# Sheet4_LCD.net
KiCad netlist of a schematic drawn in Altium Designer
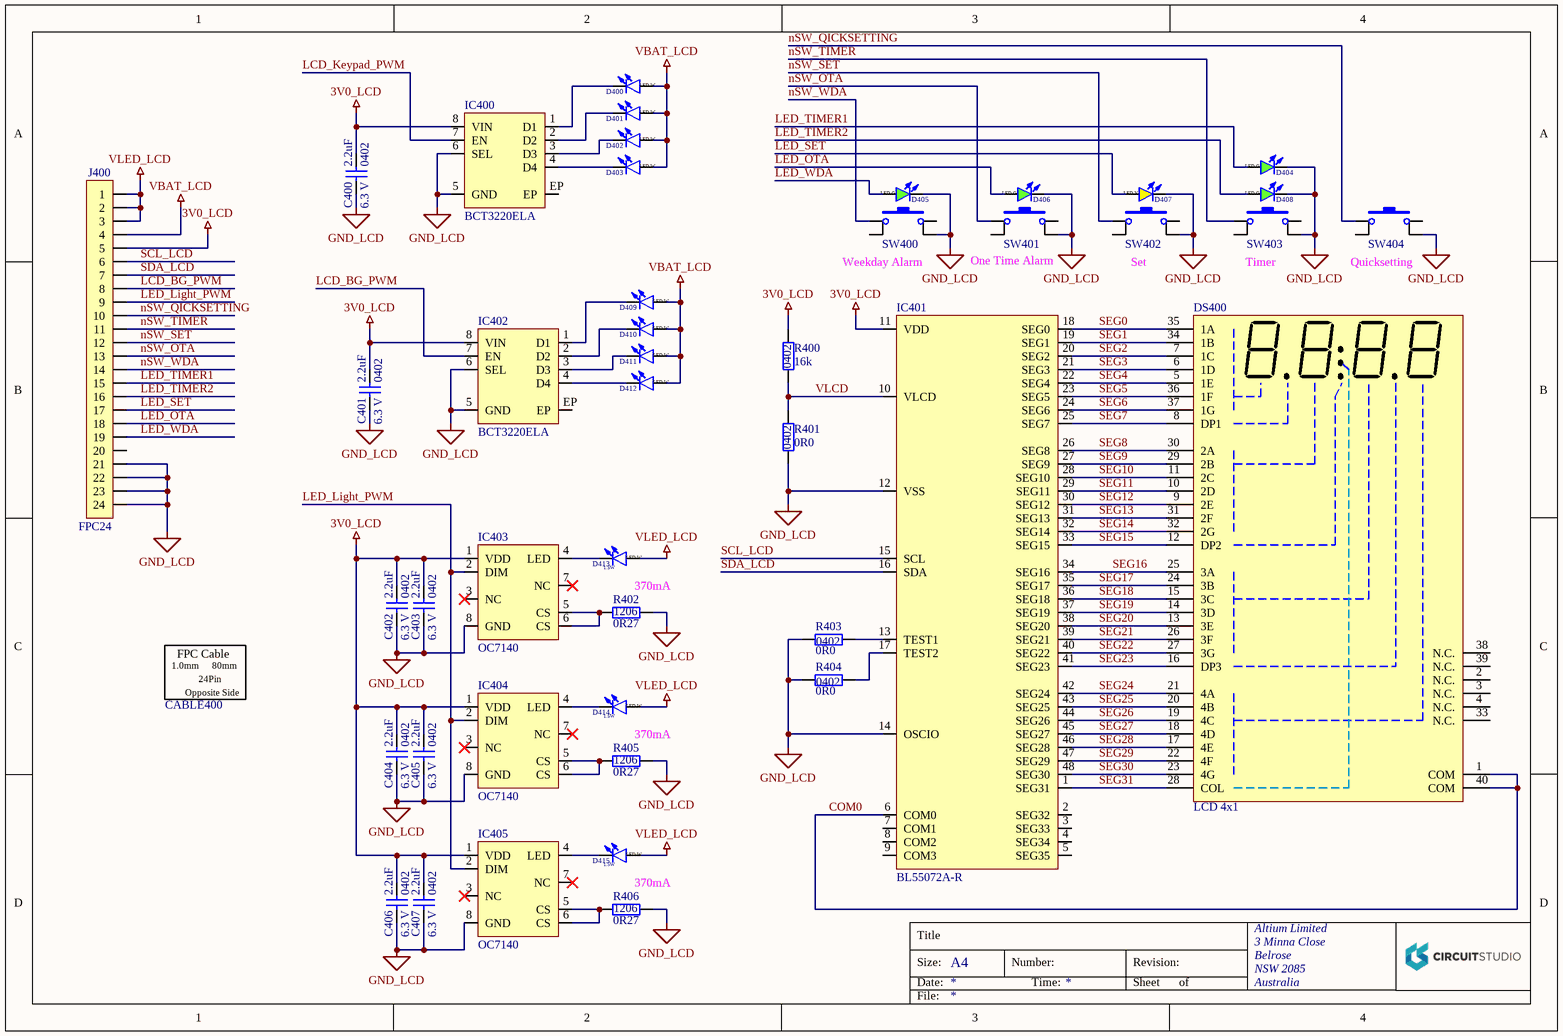
[diagram p0: Sheet4_LCD.SchDoc]

(export (version "E")
  (design (tool "Eeschema 10.0.6"))
  (components
    (comp (ref "C400")
      (value "C 2.2uF 0402 6.3V")
      (footprint "0402")
      (description "CAP CER 2.2UF 6.3V X6T 0402")
      (fields
        (field (name "MANUFACTURER") "Murata Electronics")
        (field (name "MANUFACTURER PART NUMBER") "GRM155D80J225ME95D")
        (field (name "CAPACITANCE") "2.2uF")
        (field (name "VOLTAGE") "6.3 V")
      )
      (libsource (lib "CS_Part_Library") (part "CAP_2.2uF_6V3_0402"))
    )
    (comp (ref "C401")
      (value "C 2.2uF 0402 6.3V")
      (footprint "0402")
      (description "CAP CER 2.2UF 6.3V X6T 0402")
      (fields
        (field (name "MANUFACTURER") "Murata Electronics")
        (field (name "MANUFACTURER PART NUMBER") "GRM155D80J225ME95D")
        (field (name "CAPACITANCE") "2.2uF")
        (field (name "VOLTAGE") "6.3 V")
      )
      (libsource (lib "CS_Part_Library") (part "CAP_2.2uF_6V3_0402"))
    )
    (comp (ref "C402")
      (value "C 2.2uF 0402 6.3V")
      (footprint "0402")
      (description "CAP CER 2.2UF 6.3V X6T 0402")
      (fields
        (field (name "MANUFACTURER") "Murata Electronics")
        (field (name "MANUFACTURER PART NUMBER") "GRM155D80J225ME95D")
        (field (name "CAPACITANCE") "2.2uF")
        (field (name "VOLTAGE") "6.3 V")
      )
      (libsource (lib "CS_Part_Library") (part "CAP_2.2uF_6V3_0402"))
    )
    (comp (ref "C403")
      (value "C 2.2uF 0402 6.3V")
      (footprint "0402")
      (description "CAP CER 2.2UF 6.3V X6T 0402")
      (fields
        (field (name "MANUFACTURER") "Murata Electronics")
        (field (name "MANUFACTURER PART NUMBER") "GRM155D80J225ME95D")
        (field (name "CAPACITANCE") "2.2uF")
        (field (name "VOLTAGE") "6.3 V")
      )
      (libsource (lib "CS_Part_Library") (part "CAP_2.2uF_6V3_0402"))
    )
    (comp (ref "C404")
      (value "C 2.2uF 0402 6.3V")
      (footprint "0402")
      (description "CAP CER 2.2UF 6.3V X6T 0402")
      (fields
        (field (name "MANUFACTURER") "Murata Electronics")
        (field (name "MANUFACTURER PART NUMBER") "GRM155D80J225ME95D")
        (field (name "CAPACITANCE") "2.2uF")
        (field (name "VOLTAGE") "6.3 V")
      )
      (libsource (lib "CS_Part_Library") (part "CAP_2.2uF_6V3_0402"))
    )
    (comp (ref "C405")
      (value "C 2.2uF 0402 6.3V")
      (footprint "0402")
      (description "CAP CER 2.2UF 6.3V X6T 0402")
      (fields
        (field (name "MANUFACTURER") "Murata Electronics")
        (field (name "MANUFACTURER PART NUMBER") "GRM155D80J225ME95D")
        (field (name "CAPACITANCE") "2.2uF")
        (field (name "VOLTAGE") "6.3 V")
      )
      (libsource (lib "CS_Part_Library") (part "CAP_2.2uF_6V3_0402"))
    )
    (comp (ref "C406")
      (value "C 2.2uF 0402 6.3V")
      (footprint "0402")
      (description "CAP CER 2.2UF 6.3V X6T 0402")
      (fields
        (field (name "MANUFACTURER") "Murata Electronics")
        (field (name "MANUFACTURER PART NUMBER") "GRM155D80J225ME95D")
        (field (name "CAPACITANCE") "2.2uF")
        (field (name "VOLTAGE") "6.3 V")
      )
      (libsource (lib "CS_Part_Library") (part "CAP_2.2uF_6V3_0402"))
    )
    (comp (ref "C407")
      (value "C 2.2uF 0402 6.3V")
      (footprint "0402")
      (description "CAP CER 2.2UF 6.3V X6T 0402")
      (fields
        (field (name "MANUFACTURER") "Murata Electronics")
        (field (name "MANUFACTURER PART NUMBER") "GRM155D80J225ME95D")
        (field (name "CAPACITANCE") "2.2uF")
        (field (name "VOLTAGE") "6.3 V")
      )
      (libsource (lib "CS_Part_Library") (part "CAP_2.2uF_6V3_0402"))
    )
    (comp (ref "CABLE400")
      (value "FPC24p80mm")
      (description "FPC Cable 1mm Pitch 24Pin 80mm Opposite Sides")
      (fields
        (field (name "MANUFACTURER") "LX")
        (field (name "MANUFACTURER PART NUMBER") "C50299")
        (field (name "PITCH") "1.0mm")
        (field (name "LENGTH") "80mm")
        (field (name "MODE") "Opposite Side")
        (field (name "NOOFPINS") "24Pin")
      )
      (libsource (lib "Symbols") (part "CABLE_FPC24_80"))
    )
    (comp (ref "D400")
      (value "LED W")
      (footprint "LED_99-218UMC_side")
      (description "LED WHITE SIDE SMD")
      (fields
        (field (name "MANUFACTURER") "Everlight Elec")
        (field (name "MANUFACTURER PART NUMBER") "99-218UMC/1637CD/TR8-T")
      )
      (libsource (lib "CS_Part_Library") (part "D_LED_White_s"))
    )
    (comp (ref "D401")
      (value "LED W")
      (footprint "LED_99-218UMC_side")
      (description "LED WHITE SIDE SMD")
      (fields
        (field (name "MANUFACTURER") "Everlight Elec")
        (field (name "MANUFACTURER PART NUMBER") "99-218UMC/1637CD/TR8-T")
      )
      (libsource (lib "CS_Part_Library") (part "D_LED_White_s"))
    )
    (comp (ref "D402")
      (value "LED W")
      (footprint "LED_99-218UMC_side")
      (description "LED WHITE SIDE SMD")
      (fields
        (field (name "MANUFACTURER") "Everlight Elec")
        (field (name "MANUFACTURER PART NUMBER") "99-218UMC/1637CD/TR8-T")
      )
      (libsource (lib "CS_Part_Library") (part "D_LED_White_s"))
    )
    (comp (ref "D403")
      (value "LED W")
      (footprint "LED_99-218UMC_side")
      (description "LED WHITE SIDE SMD")
      (fields
        (field (name "MANUFACTURER") "Everlight Elec")
        (field (name "MANUFACTURER PART NUMBER") "99-218UMC/1637CD/TR8-T")
      )
      (libsource (lib "CS_Part_Library") (part "D_LED_White_s"))
    )
    (comp (ref "D404")
      (value "LED G")
      (footprint "LED_0603")
      (description "LED GREEN DIFFUSED 0603 SMD")
      (fields
        (field (name "MANUFACTURER") "OSRAM Opto Semiconductors Inc.")
        (field (name "MANUFACTURER PART NUMBER") "LT Q39G-Q1OO-25-1")
      )
      (libsource (lib "CS_Part_Library") (part "D_LED_Green_0603"))
    )
    (comp (ref "D405")
      (value "LED G")
      (footprint "LED_0603")
      (description "LED GREEN DIFFUSED 0603 SMD")
      (fields
        (field (name "MANUFACTURER") "OSRAM Opto Semiconductors Inc.")
        (field (name "MANUFACTURER PART NUMBER") "LT Q39G-Q1OO-25-1")
      )
      (libsource (lib "CS_Part_Library") (part "D_LED_Green_0603"))
    )
    (comp (ref "D406")
      (value "LED G")
      (footprint "LED_0603")
      (description "LED GREEN DIFFUSED 0603 SMD")
      (fields
        (field (name "MANUFACTURER") "OSRAM Opto Semiconductors Inc.")
        (field (name "MANUFACTURER PART NUMBER") "LT Q39G-Q1OO-25-1")
      )
      (libsource (lib "CS_Part_Library") (part "D_LED_Green_0603"))
    )
    (comp (ref "D407")
      (value "LED Y")
      (footprint "LED_0603")
      (description "LED YELLOW DIFFUSED")
      (fields
        (field (name "MANUFACTURER") "Stanley Electric Co")
        (field (name "MANUFACTURER PART NUMBER") "FKY1111C-TR")
      )
      (libsource (lib "CS_Part_Library") (part "D_LED_Yellow_0603"))
    )
    (comp (ref "D408")
      (value "LED G")
      (footprint "LED_0603")
      (description "LED GREEN DIFFUSED 0603 SMD")
      (fields
        (field (name "MANUFACTURER") "OSRAM Opto Semiconductors Inc.")
        (field (name "MANUFACTURER PART NUMBER") "LT Q39G-Q1OO-25-1")
      )
      (libsource (lib "CS_Part_Library") (part "D_LED_Green_0603"))
    )
    (comp (ref "D409")
      (value "LED W")
      (footprint "LED_99-218UMC_side")
      (description "LED WHITE SIDE SMD")
      (fields
        (field (name "MANUFACTURER") "Everlight Elec")
        (field (name "MANUFACTURER PART NUMBER") "99-218UMC/1637CD/TR8-T")
      )
      (libsource (lib "CS_Part_Library") (part "D_LED_White_s"))
    )
    (comp (ref "D410")
      (value "LED W")
      (footprint "LED_99-218UMC_side")
      (description "LED WHITE SIDE SMD")
      (fields
        (field (name "MANUFACTURER") "Everlight Elec")
        (field (name "MANUFACTURER PART NUMBER") "99-218UMC/1637CD/TR8-T")
      )
      (libsource (lib "CS_Part_Library") (part "D_LED_White_s"))
    )
    (comp (ref "D411")
      (value "LED W")
      (footprint "LED_99-218UMC_side")
      (description "LED WHITE SIDE SMD")
      (fields
        (field (name "MANUFACTURER") "Everlight Elec")
        (field (name "MANUFACTURER PART NUMBER") "99-218UMC/1637CD/TR8-T")
      )
      (libsource (lib "CS_Part_Library") (part "D_LED_White_s"))
    )
    (comp (ref "D412")
      (value "LED W")
      (footprint "LED_99-218UMC_side")
      (description "LED WHITE SIDE SMD")
      (fields
        (field (name "MANUFACTURER") "Everlight Elec")
        (field (name "MANUFACTURER PART NUMBER") "99-218UMC/1637CD/TR8-T")
      )
      (libsource (lib "CS_Part_Library") (part "D_LED_White_s"))
    )
    (comp (ref "D413")
      (value "LED W")
      (footprint "LED_3.5x3.15")
      (description "LED XLAMP WARM WHITE 3250K 4SMD")
      (fields
        (field (name "MANUFACTURER") "CreeLED, Inc.")
        (field (name "MANUFACTURER PART NUMBER") "MLEAWT-A1-0000-0003F7")
        (field (name "POWER") "1.5W")
      )
      (libsource (lib "CS_Part_Library") (part "D_LED_W_HP"))
    )
    (comp (ref "D414")
      (value "LED W")
      (footprint "LED_3.5x3.15")
      (description "LED XLAMP WARM WHITE 3250K 4SMD")
      (fields
        (field (name "MANUFACTURER") "CreeLED, Inc.")
        (field (name "MANUFACTURER PART NUMBER") "MLEAWT-A1-0000-0003F7")
        (field (name "POWER") "1.5W")
      )
      (libsource (lib "CS_Part_Library") (part "D_LED_W_HP"))
    )
    (comp (ref "D415")
      (value "LED W")
      (footprint "LED_3.5x3.15")
      (description "LED XLAMP WARM WHITE 3250K 4SMD")
      (fields
        (field (name "MANUFACTURER") "CreeLED, Inc.")
        (field (name "MANUFACTURER PART NUMBER") "MLEAWT-A1-0000-0003F7")
        (field (name "POWER") "1.5W")
      )
      (libsource (lib "CS_Part_Library") (part "D_LED_W_HP"))
    )
    (comp (ref "DS400")
      (value "LCD 4x1")
      (footprint "DISPL_7SEG_4")
      (description "LCD MOD 4 DIG 4 X 1 REFLECTIVE")
      (fields
        (field (name "MANUFACTURER") "Varitronix")
        (field (name "MANUFACTURER PART NUMBER") "VI-402-DP-RC-S")
      )
      (libsource (lib "Symbols") (part "DISPL_7SEG_4x1"))
    )
    (comp (ref "IC400")
      (value "BCT3220ELA")
      (footprint "VDFN-8-EP_2x2")
      (description "IC LED DRIVER 4 CH")
      (fields
        (field (name "MANUFACTURER") "BROADCHIP")
        (field (name "MANUFACTURER PART NUMBER") "BCT3220ELA-TR")
      )
      (libsource (lib "Symbols") (part "IC_LED_cntr_BCT3220ELA"))
    )
    (comp (ref "IC401")
      (value "BL55072A-R")
      (footprint "TSSOP-48")
      (description "IC LCD DRIVER 36SEG TSSOP-48")
      (fields (field (name "MANUFACTURER") "BL(Shanghai Belling)"))
      (libsource (lib "Symbols") (part "IC_LCD_cntr_BL55072A-R"))
    )
    (comp (ref "IC402")
      (value "BCT3220ELA")
      (footprint "VDFN-8-EP_2x2")
      (description "IC LED DRIVER 4 CH")
      (fields
        (field (name "MANUFACTURER") "BROADCHIP")
        (field (name "MANUFACTURER PART NUMBER") "BCT3220ELA-TR")
      )
      (libsource (lib "Symbols") (part "IC_LED_cntr_BCT3220ELA"))
    )
    (comp (ref "IC403")
      (value "OC7140")
      (footprint "SOIC-8-EP")
      (description "IC LED DRIVER 1 CH 2A ESOP8")
      (fields (field (name "MANUFACTURER") "OCX"))
      (libsource (lib "CS_Part_Library") (part "IC_LED_cntr_OC7140"))
    )
    (comp (ref "IC404")
      (value "OC7140")
      (footprint "SOIC-8-EP")
      (description "IC LED DRIVER 1 CH 2A ESOP8")
      (fields (field (name "MANUFACTURER") "OCX"))
      (libsource (lib "CS_Part_Library") (part "IC_LED_cntr_OC7140"))
    )
    (comp (ref "IC405")
      (value "OC7140")
      (footprint "SOIC-8-EP")
      (description "IC LED DRIVER 1 CH 2A ESOP8")
      (fields (field (name "MANUFACTURER") "OCX"))
      (libsource (lib "CS_Part_Library") (part "IC_LED_cntr_OC7140"))
    )
    (comp (ref "J400")
      (value "FPC24")
      (footprint "J_FPC_522712479")
      (description "CONN FPC BOT 24 PIN 1mm Pitch")
      (fields (field (name "MANUFACTURER") "MOLEX") (field (name "MANUFACTURER PART NUMBER") "522712479"))
      (libsource (lib "Symbols") (part "J_FPC24_DS"))
    )
    (comp (ref "R400")
      (value "R 16k 0402")
      (footprint "0402")
      (description "RES 16K OHM 1% 1/16W 0402")
      (fields
        (field (name "MANUFACTURER") "Stackpole Electronics Inc")
        (field (name "MANUFACTURER PART NUMBER") "RMCF0402FT16K0")
        (field (name "RESISTANCE") "16k")
      )
      (libsource (lib "CS_Part_Library") (part "R_16k_0402"))
    )
    (comp (ref "R401")
      (value "R 0R0 0402")
      (footprint "0402")
      (description "RES 0 OHM JUMPER 1/16W 0402")
      (fields
        (field (name "MANUFACTURER") "Stackpole Electronics Inc")
        (field (name "MANUFACTURER PART NUMBER") "RMCF0402ZT0R00")
        (field (name "RESISTANCE") "0R0")
      )
      (libsource (lib "") (part "R_0R0_0402_1"))
    )
    (comp (ref "R402")
      (value "R 0R27 1206")
      (footprint "1206")
      (description "RES 0.27 OHM 1% 1/3W 1206")
      (fields
        (field (name "MANUFACTURER") "RALEC")
        (field (name "MANUFACTURER PART NUMBER") "RTT06R270FTP")
        (field (name "RESISTANCE") "0R27")
      )
      (libsource (lib "CS_Part_Library") (part "R_0R27_1206"))
    )
    (comp (ref "R403")
      (value "R 0R0 0402")
      (footprint "0402")
      (description "RES 0 OHM JUMPER 1/16W 0402")
      (fields
        (field (name "MANUFACTURER") "Stackpole Electronics Inc")
        (field (name "MANUFACTURER PART NUMBER") "RMCF0402ZT0R00")
        (field (name "RESISTANCE") "0R0")
      )
      (libsource (lib "CS_Part_Library") (part "R_0R0_0402"))
    )
    (comp (ref "R404")
      (value "R 0R0 0402")
      (footprint "0402")
      (description "RES 0 OHM JUMPER 1/16W 0402")
      (fields
        (field (name "MANUFACTURER") "Stackpole Electronics Inc")
        (field (name "MANUFACTURER PART NUMBER") "RMCF0402ZT0R00")
        (field (name "RESISTANCE") "0R0")
      )
      (libsource (lib "CS_Part_Library") (part "R_0R0_0402"))
    )
    (comp (ref "R405")
      (value "R 0R27 1206")
      (footprint "1206")
      (description "RES 0.27 OHM 1% 1/3W 1206")
      (fields
        (field (name "MANUFACTURER") "RALEC")
        (field (name "MANUFACTURER PART NUMBER") "RTT06R270FTP")
        (field (name "RESISTANCE") "0R27")
      )
      (libsource (lib "CS_Part_Library") (part "R_0R27_1206"))
    )
    (comp (ref "R406")
      (value "R 0R27 1206")
      (footprint "1206")
      (description "RES 0.27 OHM 1% 1/3W 1206")
      (fields
        (field (name "MANUFACTURER") "RALEC")
        (field (name "MANUFACTURER PART NUMBER") "RTT06R270FTP")
        (field (name "RESISTANCE") "0R27")
      )
      (libsource (lib "CS_Part_Library") (part "R_0R27_1206"))
    )
    (comp (ref "SW400")
      (value "SW")
      (footprint "SW_BRIGHT_6.1x6.1")
      (description "SWITCH TACTILE SW-SMD")
      (fields
        (field (name "MANUFACTURER") "BRIGHT")
        (field (name "MANUFACTURER PART NUMBER") "TSA063G50-250")
      )
      (libsource (lib "CS_Part_Library") (part "SW_TactileSW_V_2"))
    )
    (comp (ref "SW401")
      (value "SW")
      (footprint "SW_BRIGHT_6.1x6.1")
      (description "SWITCH TACTILE SW-SMD")
      (fields
        (field (name "MANUFACTURER") "BRIGHT")
        (field (name "MANUFACTURER PART NUMBER") "TSA063G50-250")
      )
      (libsource (lib "CS_Part_Library") (part "SW_TactileSW_V_2"))
    )
    (comp (ref "SW402")
      (value "SW")
      (footprint "SW_BRIGHT_6.1x6.1")
      (description "SWITCH TACTILE SW-SMD")
      (fields
        (field (name "MANUFACTURER") "BRIGHT")
        (field (name "MANUFACTURER PART NUMBER") "TSA063G50-250")
      )
      (libsource (lib "CS_Part_Library") (part "SW_TactileSW_V_2"))
    )
    (comp (ref "SW403")
      (value "SW")
      (footprint "SW_BRIGHT_6.1x6.1")
      (description "SWITCH TACTILE SW-SMD")
      (fields
        (field (name "MANUFACTURER") "BRIGHT")
        (field (name "MANUFACTURER PART NUMBER") "TSA063G50-250")
      )
      (libsource (lib "CS_Part_Library") (part "SW_TactileSW_V_2"))
    )
    (comp (ref "SW404")
      (value "SW")
      (footprint "SW_BRIGHT_6.1x6.1")
      (description "SWITCH TACTILE SW-SMD")
      (fields
        (field (name "MANUFACTURER") "BRIGHT")
        (field (name "MANUFACTURER PART NUMBER") "TSA063G50-250")
      )
      (libsource (lib "CS_Part_Library") (part "SW_TactileSW_V_2"))
    )
  )
  (nets
    (net (code "1") (name "/COM0") (class "Default")
      (node (ref "DS400") (pin "1") (pinfunction "COM_1") (pintype "passive"))
      (node (ref "DS400") (pin "40") (pinfunction "COM_40") (pintype "passive"))
      (node (ref "IC401") (pin "6") (pinfunction "COM0_6") (pintype "passive"))
    )
    (net (code "2") (name "/LCD_BG_PWM") (class "Default")
      (node (ref "IC402") (pin "7") (pinfunction "EN_7") (pintype "passive"))
      (node (ref "J400") (pin "8") (pinfunction "8_8") (pintype "passive"))
    )
    (net (code "3") (name "/LCD_Keypad_PWM") (class "Default")
      (node (ref "IC400") (pin "7") (pinfunction "EN_7") (pintype "passive"))
    )
    (net (code "4") (name "/LED_Light_PWM") (class "Default")
      (node (ref "IC403") (pin "2") (pinfunction "DIM_2") (pintype "passive"))
      (node (ref "IC404") (pin "2") (pinfunction "DIM_2") (pintype "passive"))
      (node (ref "IC405") (pin "2") (pinfunction "DIM_2") (pintype "passive"))
      (node (ref "J400") (pin "9") (pinfunction "9_9") (pintype "passive"))
    )
    (net (code "5") (name "/LED_OTA") (class "Default")
      (node (ref "D406") (pin "A") (pinfunction "A_A") (pintype "passive"))
      (node (ref "J400") (pin "18") (pinfunction "18_18") (pintype "passive"))
    )
    (net (code "6") (name "/LED_SET") (class "Default")
      (node (ref "D407") (pin "A") (pinfunction "A_A") (pintype "passive"))
      (node (ref "J400") (pin "17") (pinfunction "17_17") (pintype "passive"))
    )
    (net (code "7") (name "/LED_TIMER1") (class "Default")
      (node (ref "D404") (pin "A") (pinfunction "A_A") (pintype "passive"))
      (node (ref "J400") (pin "15") (pinfunction "15_15") (pintype "passive"))
    )
    (net (code "8") (name "/LED_TIMER2") (class "Default")
      (node (ref "D408") (pin "A") (pinfunction "A_A") (pintype "passive"))
      (node (ref "J400") (pin "16") (pinfunction "16_16") (pintype "passive"))
    )
    (net (code "9") (name "/LED_WDA") (class "Default")
      (node (ref "D405") (pin "A") (pinfunction "A_A") (pintype "passive"))
      (node (ref "J400") (pin "19") (pinfunction "19_19") (pintype "passive"))
    )
    (net (code "10") (name "/SCL_LCD") (class "Default")
      (node (ref "IC401") (pin "15") (pinfunction "SCL_15") (pintype "passive"))
      (node (ref "J400") (pin "6") (pinfunction "6_6") (pintype "passive"))
    )
    (net (code "11") (name "/SDA_LCD") (class "Default")
      (node (ref "IC401") (pin "16") (pinfunction "SDA_16") (pintype "passive"))
      (node (ref "J400") (pin "7") (pinfunction "7_7") (pintype "passive"))
    )
    (net (code "12") (name "/SEG0") (class "Default")
      (node (ref "DS400") (pin "35") (pinfunction "1A_35") (pintype "passive"))
      (node (ref "IC401") (pin "18") (pinfunction "SEG0_18") (pintype "passive"))
    )
    (net (code "13") (name "/SEG1") (class "Default")
      (node (ref "DS400") (pin "34") (pinfunction "1B_34") (pintype "passive"))
      (node (ref "IC401") (pin "19") (pinfunction "SEG1_19") (pintype "passive"))
    )
    (net (code "14") (name "/SEG2") (class "Default")
      (node (ref "DS400") (pin "7") (pinfunction "1C_7") (pintype "passive"))
      (node (ref "IC401") (pin "20") (pinfunction "SEG2_20") (pintype "passive"))
    )
    (net (code "15") (name "/SEG3") (class "Default")
      (node (ref "DS400") (pin "6") (pinfunction "1D_6") (pintype "passive"))
      (node (ref "IC401") (pin "21") (pinfunction "SEG3_21") (pintype "passive"))
    )
    (net (code "16") (name "/SEG4") (class "Default")
      (node (ref "DS400") (pin "5") (pinfunction "1E_5") (pintype "passive"))
      (node (ref "IC401") (pin "22") (pinfunction "SEG4_22") (pintype "passive"))
    )
    (net (code "17") (name "/SEG5") (class "Default")
      (node (ref "DS400") (pin "36") (pinfunction "1F_36") (pintype "passive"))
      (node (ref "IC401") (pin "23") (pinfunction "SEG5_23") (pintype "passive"))
    )
    (net (code "18") (name "/SEG6") (class "Default")
      (node (ref "DS400") (pin "37") (pinfunction "1G_37") (pintype "passive"))
      (node (ref "IC401") (pin "24") (pinfunction "SEG6_24") (pintype "passive"))
    )
    (net (code "19") (name "/SEG7") (class "Default")
      (node (ref "DS400") (pin "8") (pinfunction "DP1_8") (pintype "passive"))
      (node (ref "IC401") (pin "25") (pinfunction "SEG7_25") (pintype "passive"))
    )
    (net (code "20") (name "/SEG8") (class "Default")
      (node (ref "DS400") (pin "30") (pinfunction "2A_30") (pintype "passive"))
      (node (ref "IC401") (pin "26") (pinfunction "SEG8_26") (pintype "passive"))
    )
    (net (code "21") (name "/SEG9") (class "Default")
      (node (ref "DS400") (pin "29") (pinfunction "2B_29") (pintype "passive"))
      (node (ref "IC401") (pin "27") (pinfunction "SEG9_27") (pintype "passive"))
    )
    (net (code "22") (name "/SEG10") (class "Default")
      (node (ref "DS400") (pin "11") (pinfunction "2C_11") (pintype "passive"))
      (node (ref "IC401") (pin "28") (pinfunction "SEG10_28") (pintype "passive"))
    )
    (net (code "23") (name "/SEG11") (class "Default")
      (node (ref "DS400") (pin "10") (pinfunction "2D_10") (pintype "passive"))
      (node (ref "IC401") (pin "29") (pinfunction "SEG11_29") (pintype "passive"))
    )
    (net (code "24") (name "/SEG12") (class "Default")
      (node (ref "DS400") (pin "9") (pinfunction "2E_9") (pintype "passive"))
      (node (ref "IC401") (pin "30") (pinfunction "SEG12_30") (pintype "passive"))
    )
    (net (code "25") (name "/SEG13") (class "Default")
      (node (ref "DS400") (pin "31") (pinfunction "2F_31") (pintype "passive"))
      (node (ref "IC401") (pin "31") (pinfunction "SEG13_31") (pintype "passive"))
    )
    (net (code "26") (name "/SEG14") (class "Default")
      (node (ref "DS400") (pin "32") (pinfunction "2G_32") (pintype "passive"))
      (node (ref "IC401") (pin "32") (pinfunction "SEG14_32") (pintype "passive"))
    )
    (net (code "27") (name "/SEG15") (class "Default")
      (node (ref "DS400") (pin "12") (pinfunction "DP2_12") (pintype "passive"))
      (node (ref "IC401") (pin "33") (pinfunction "SEG15_33") (pintype "passive"))
    )
    (net (code "28") (name "/SEG16") (class "Default")
      (node (ref "DS400") (pin "25") (pinfunction "3A_25") (pintype "passive"))
      (node (ref "IC401") (pin "34") (pinfunction "SEG16_34") (pintype "passive"))
    )
    (net (code "29") (name "/SEG17") (class "Default")
      (node (ref "DS400") (pin "24") (pinfunction "3B_24") (pintype "passive"))
      (node (ref "IC401") (pin "35") (pinfunction "SEG17_35") (pintype "passive"))
    )
    (net (code "30") (name "/SEG18") (class "Default")
      (node (ref "DS400") (pin "15") (pinfunction "3C_15") (pintype "passive"))
      (node (ref "IC401") (pin "36") (pinfunction "SEG18_36") (pintype "passive"))
    )
    (net (code "31") (name "/SEG19") (class "Default")
      (node (ref "DS400") (pin "14") (pinfunction "3D_14") (pintype "passive"))
      (node (ref "IC401") (pin "37") (pinfunction "SEG19_37") (pintype "passive"))
    )
    (net (code "32") (name "/SEG20") (class "Default")
      (node (ref "DS400") (pin "13") (pinfunction "3E_13") (pintype "passive"))
      (node (ref "IC401") (pin "38") (pinfunction "SEG20_38") (pintype "passive"))
    )
    (net (code "33") (name "/SEG21") (class "Default")
      (node (ref "DS400") (pin "26") (pinfunction "3F_26") (pintype "passive"))
      (node (ref "IC401") (pin "39") (pinfunction "SEG21_39") (pintype "passive"))
    )
    (net (code "34") (name "/SEG22") (class "Default")
      (node (ref "DS400") (pin "27") (pinfunction "3G_27") (pintype "passive"))
      (node (ref "IC401") (pin "40") (pinfunction "SEG22_40") (pintype "passive"))
    )
    (net (code "35") (name "/SEG23") (class "Default")
      (node (ref "DS400") (pin "16") (pinfunction "DP3_16") (pintype "passive"))
      (node (ref "IC401") (pin "41") (pinfunction "SEG23_41") (pintype "passive"))
    )
    (net (code "36") (name "/SEG24") (class "Default")
      (node (ref "DS400") (pin "21") (pinfunction "4A_21") (pintype "passive"))
      (node (ref "IC401") (pin "42") (pinfunction "SEG24_42") (pintype "passive"))
    )
    (net (code "37") (name "/SEG25") (class "Default")
      (node (ref "DS400") (pin "20") (pinfunction "4B_20") (pintype "passive"))
      (node (ref "IC401") (pin "43") (pinfunction "SEG25_43") (pintype "passive"))
    )
    (net (code "38") (name "/SEG26") (class "Default")
      (node (ref "DS400") (pin "19") (pinfunction "4C_19") (pintype "passive"))
      (node (ref "IC401") (pin "44") (pinfunction "SEG26_44") (pintype "passive"))
    )
    (net (code "39") (name "/SEG27") (class "Default")
      (node (ref "DS400") (pin "18") (pinfunction "4D_18") (pintype "passive"))
      (node (ref "IC401") (pin "45") (pinfunction "SEG27_45") (pintype "passive"))
    )
    (net (code "40") (name "/SEG28") (class "Default")
      (node (ref "DS400") (pin "17") (pinfunction "4E_17") (pintype "passive"))
      (node (ref "IC401") (pin "46") (pinfunction "SEG28_46") (pintype "passive"))
    )
    (net (code "41") (name "/SEG29") (class "Default")
      (node (ref "DS400") (pin "22") (pinfunction "4F_22") (pintype "passive"))
      (node (ref "IC401") (pin "47") (pinfunction "SEG29_47") (pintype "passive"))
    )
    (net (code "42") (name "/SEG30") (class "Default")
      (node (ref "DS400") (pin "23") (pinfunction "4G_23") (pintype "passive"))
      (node (ref "IC401") (pin "48") (pinfunction "SEG30_48") (pintype "passive"))
    )
    (net (code "43") (name "/SEG31") (class "Default")
      (node (ref "DS400") (pin "28") (pinfunction "COL_28") (pintype "passive"))
      (node (ref "IC401") (pin "1") (pinfunction "SEG31_1") (pintype "passive"))
    )
    (net (code "44") (name "/VLCD") (class "Default")
      (node (ref "IC401") (pin "10") (pinfunction "VLCD_10") (pintype "passive"))
      (node (ref "R400") (pin "1") (pinfunction "1_1") (pintype "passive"))
      (node (ref "R401") (pin "2") (pinfunction "2_2") (pintype "passive"))
    )
    (net (code "45") (name "/nSW_OTA") (class "Default")
      (node (ref "J400") (pin "13") (pinfunction "13_13") (pintype "passive"))
      (node (ref "SW401") (pin "1") (pinfunction "1_1") (pintype "passive"))
    )
    (net (code "46") (name "/nSW_QICKSETTING") (class "Default")
      (node (ref "J400") (pin "10") (pinfunction "10_10") (pintype "passive"))
      (node (ref "SW404") (pin "1") (pinfunction "1_1") (pintype "passive"))
    )
    (net (code "47") (name "/nSW_SET") (class "Default")
      (node (ref "J400") (pin "12") (pinfunction "12_12") (pintype "passive"))
      (node (ref "SW402") (pin "1") (pinfunction "1_1") (pintype "passive"))
    )
    (net (code "48") (name "/nSW_TIMER") (class "Default")
      (node (ref "J400") (pin "11") (pinfunction "11_11") (pintype "passive"))
      (node (ref "SW403") (pin "1") (pinfunction "1_1") (pintype "passive"))
    )
    (net (code "49") (name "/nSW_WDA") (class "Default")
      (node (ref "J400") (pin "14") (pinfunction "14_14") (pintype "passive"))
      (node (ref "SW400") (pin "1") (pinfunction "1_1") (pintype "passive"))
    )
    (net (code "50") (name "3V0_LCD") (class "Default")
      (node (ref "C400") (pin "2") (pinfunction "2_2") (pintype "passive"))
      (node (ref "C401") (pin "2") (pinfunction "2_2") (pintype "passive"))
      (node (ref "C402") (pin "2") (pinfunction "2_2") (pintype "passive"))
      (node (ref "C403") (pin "2") (pinfunction "2_2") (pintype "passive"))
      (node (ref "C404") (pin "2") (pinfunction "2_2") (pintype "passive"))
      (node (ref "C405") (pin "2") (pinfunction "2_2") (pintype "passive"))
      (node (ref "C406") (pin "2") (pinfunction "2_2") (pintype "passive"))
      (node (ref "C407") (pin "2") (pinfunction "2_2") (pintype "passive"))
      (node (ref "IC400") (pin "8") (pinfunction "VIN_8") (pintype "passive"))
      (node (ref "IC401") (pin "11") (pinfunction "VDD_11") (pintype "passive"))
      (node (ref "IC402") (pin "8") (pinfunction "VIN_8") (pintype "passive"))
      (node (ref "IC403") (pin "1") (pinfunction "VDD_1") (pintype "passive"))
      (node (ref "IC404") (pin "1") (pinfunction "VDD_1") (pintype "passive"))
      (node (ref "IC405") (pin "1") (pinfunction "VDD_1") (pintype "passive"))
      (node (ref "J400") (pin "5") (pinfunction "5_5") (pintype "passive"))
      (node (ref "R400") (pin "2") (pinfunction "2_2") (pintype "passive"))
    )
    (net (code "51") (name "GND_LCD") (class "Default")
      (node (ref "C400") (pin "1") (pinfunction "1_1") (pintype "passive"))
      (node (ref "C401") (pin "1") (pinfunction "1_1") (pintype "passive"))
      (node (ref "C402") (pin "1") (pinfunction "1_1") (pintype "passive"))
      (node (ref "C403") (pin "1") (pinfunction "1_1") (pintype "passive"))
      (node (ref "C404") (pin "1") (pinfunction "1_1") (pintype "passive"))
      (node (ref "C405") (pin "1") (pinfunction "1_1") (pintype "passive"))
      (node (ref "C406") (pin "1") (pinfunction "1_1") (pintype "passive"))
      (node (ref "C407") (pin "1") (pinfunction "1_1") (pintype "passive"))
      (node (ref "D404") (pin "K") (pinfunction "K_K") (pintype "passive"))
      (node (ref "D405") (pin "K") (pinfunction "K_K") (pintype "passive"))
      (node (ref "D406") (pin "K") (pinfunction "K_K") (pintype "passive"))
      (node (ref "D407") (pin "K") (pinfunction "K_K") (pintype "passive"))
      (node (ref "D408") (pin "K") (pinfunction "K_K") (pintype "passive"))
      (node (ref "IC400") (pin "5") (pinfunction "GND_5") (pintype "passive"))
      (node (ref "IC400") (pin "6") (pinfunction "SEL_6") (pintype "passive"))
      (node (ref "IC401") (pin "12") (pinfunction "VSS_12") (pintype "passive"))
      (node (ref "IC401") (pin "14") (pinfunction "OSCIO_14") (pintype "passive"))
      (node (ref "IC402") (pin "5") (pinfunction "GND_5") (pintype "passive"))
      (node (ref "IC402") (pin "6") (pinfunction "SEL_6") (pintype "passive"))
      (node (ref "IC403") (pin "8") (pinfunction "GND_8") (pintype "passive"))
      (node (ref "IC404") (pin "8") (pinfunction "GND_8") (pintype "passive"))
      (node (ref "IC405") (pin "8") (pinfunction "GND_8") (pintype "passive"))
      (node (ref "J400") (pin "21") (pinfunction "21_21") (pintype "passive"))
      (node (ref "J400") (pin "22") (pinfunction "22_22") (pintype "passive"))
      (node (ref "J400") (pin "23") (pinfunction "23_23") (pintype "passive"))
      (node (ref "J400") (pin "24") (pinfunction "24_24") (pintype "passive"))
      (node (ref "R401") (pin "1") (pinfunction "1_1") (pintype "passive"))
      (node (ref "R402") (pin "2") (pinfunction "2_2") (pintype "passive"))
      (node (ref "R403") (pin "2") (pinfunction "2_2") (pintype "passive"))
      (node (ref "R404") (pin "2") (pinfunction "2_2") (pintype "passive"))
      (node (ref "R405") (pin "2") (pinfunction "2_2") (pintype "passive"))
      (node (ref "R406") (pin "2") (pinfunction "2_2") (pintype "passive"))
      (node (ref "SW400") (pin "4") (pinfunction "4_4") (pintype "passive"))
      (node (ref "SW401") (pin "4") (pinfunction "4_4") (pintype "passive"))
      (node (ref "SW402") (pin "4") (pinfunction "4_4") (pintype "passive"))
      (node (ref "SW403") (pin "4") (pinfunction "4_4") (pintype "passive"))
      (node (ref "SW404") (pin "4") (pinfunction "4_4") (pintype "passive"))
    )
    (net (code "52") (name "Net-(D400-K)") (class "Default")
      (node (ref "D400") (pin "1") (pinfunction "K_1") (pintype "passive"))
      (node (ref "IC400") (pin "1") (pinfunction "D1_1") (pintype "passive"))
    )
    (net (code "53") (name "Net-(D401-K)") (class "Default")
      (node (ref "D401") (pin "1") (pinfunction "K_1") (pintype "passive"))
      (node (ref "IC400") (pin "2") (pinfunction "D2_2") (pintype "passive"))
    )
    (net (code "54") (name "Net-(D402-K)") (class "Default")
      (node (ref "D402") (pin "1") (pinfunction "K_1") (pintype "passive"))
      (node (ref "IC400") (pin "3") (pinfunction "D3_3") (pintype "passive"))
    )
    (net (code "55") (name "Net-(D403-K)") (class "Default")
      (node (ref "D403") (pin "1") (pinfunction "K_1") (pintype "passive"))
      (node (ref "IC400") (pin "4") (pinfunction "D4_4") (pintype "passive"))
    )
    (net (code "56") (name "Net-(D409-K)") (class "Default")
      (node (ref "D409") (pin "1") (pinfunction "K_1") (pintype "passive"))
      (node (ref "IC402") (pin "1") (pinfunction "D1_1") (pintype "passive"))
    )
    (net (code "57") (name "Net-(D410-K)") (class "Default")
      (node (ref "D410") (pin "1") (pinfunction "K_1") (pintype "passive"))
      (node (ref "IC402") (pin "2") (pinfunction "D2_2") (pintype "passive"))
    )
    (net (code "58") (name "Net-(D411-K)") (class "Default")
      (node (ref "D411") (pin "1") (pinfunction "K_1") (pintype "passive"))
      (node (ref "IC402") (pin "3") (pinfunction "D3_3") (pintype "passive"))
    )
    (net (code "59") (name "Net-(D412-K)") (class "Default")
      (node (ref "D412") (pin "1") (pinfunction "K_1") (pintype "passive"))
      (node (ref "IC402") (pin "4") (pinfunction "D4_4") (pintype "passive"))
    )
    (net (code "60") (name "Net-(IC401-TEST1)") (class "Default")
      (node (ref "IC401") (pin "13") (pinfunction "TEST1_13") (pintype "passive"))
      (node (ref "R403") (pin "1") (pinfunction "1_1") (pintype "passive"))
    )
    (net (code "61") (name "Net-(IC401-TEST2)") (class "Default")
      (node (ref "IC401") (pin "17") (pinfunction "TEST2_17") (pintype "passive"))
      (node (ref "R404") (pin "1") (pinfunction "1_1") (pintype "passive"))
    )
    (net (code "62") (name "Net-(IC403-CS-Pad5)") (class "Default")
      (node (ref "IC403") (pin "5") (pinfunction "CS_5") (pintype "passive"))
      (node (ref "IC403") (pin "6") (pinfunction "CS_6") (pintype "passive"))
      (node (ref "R402") (pin "1") (pinfunction "1_1") (pintype "passive"))
    )
    (net (code "63") (name "Net-(IC403-LED)") (class "Default")
      (node (ref "D413") (pin "K") (pinfunction "K_K") (pintype "passive"))
      (node (ref "IC403") (pin "4") (pinfunction "LED_4") (pintype "passive"))
    )
    (net (code "64") (name "Net-(IC404-CS-Pad5)") (class "Default")
      (node (ref "IC404") (pin "5") (pinfunction "CS_5") (pintype "passive"))
      (node (ref "IC404") (pin "6") (pinfunction "CS_6") (pintype "passive"))
      (node (ref "R405") (pin "1") (pinfunction "1_1") (pintype "passive"))
    )
    (net (code "65") (name "Net-(IC404-LED)") (class "Default")
      (node (ref "D414") (pin "K") (pinfunction "K_K") (pintype "passive"))
      (node (ref "IC404") (pin "4") (pinfunction "LED_4") (pintype "passive"))
    )
    (net (code "66") (name "Net-(IC405-CS-Pad5)") (class "Default")
      (node (ref "IC405") (pin "5") (pinfunction "CS_5") (pintype "passive"))
      (node (ref "IC405") (pin "6") (pinfunction "CS_6") (pintype "passive"))
      (node (ref "R406") (pin "1") (pinfunction "1_1") (pintype "passive"))
    )
    (net (code "67") (name "Net-(IC405-LED)") (class "Default")
      (node (ref "D415") (pin "K") (pinfunction "K_K") (pintype "passive"))
      (node (ref "IC405") (pin "4") (pinfunction "LED_4") (pintype "passive"))
    )
    (net (code "68") (name "VBAT_LCD") (class "Default")
      (node (ref "D400") (pin "2") (pinfunction "A_2") (pintype "passive"))
      (node (ref "D401") (pin "2") (pinfunction "A_2") (pintype "passive"))
      (node (ref "D402") (pin "2") (pinfunction "A_2") (pintype "passive"))
      (node (ref "D403") (pin "2") (pinfunction "A_2") (pintype "passive"))
      (node (ref "D409") (pin "2") (pinfunction "A_2") (pintype "passive"))
      (node (ref "D410") (pin "2") (pinfunction "A_2") (pintype "passive"))
      (node (ref "D411") (pin "2") (pinfunction "A_2") (pintype "passive"))
      (node (ref "D412") (pin "2") (pinfunction "A_2") (pintype "passive"))
      (node (ref "J400") (pin "4") (pinfunction "4_4") (pintype "passive"))
    )
    (net (code "69") (name "VLED_LCD") (class "Default")
      (node (ref "D413") (pin "A") (pinfunction "A_A") (pintype "passive"))
      (node (ref "D414") (pin "A") (pinfunction "A_A") (pintype "passive"))
      (node (ref "D415") (pin "A") (pinfunction "A_A") (pintype "passive"))
      (node (ref "J400") (pin "1") (pinfunction "1_1") (pintype "passive"))
      (node (ref "J400") (pin "2") (pinfunction "2_2") (pintype "passive"))
      (node (ref "J400") (pin "3") (pinfunction "3_3") (pintype "passive"))
    )
    (net (code "70") (name "unconnected-(DS400-N.C.-Pad2)") (class "Default")
      (node (ref "DS400") (pin "2") (pinfunction "N.C._2") (pintype "passive"))
    )
    (net (code "71") (name "unconnected-(DS400-N.C.-Pad3)") (class "Default")
      (node (ref "DS400") (pin "3") (pinfunction "N.C._3") (pintype "passive"))
    )
    (net (code "72") (name "unconnected-(DS400-N.C.-Pad4)") (class "Default")
      (node (ref "DS400") (pin "4") (pinfunction "N.C._4") (pintype "passive"))
    )
    (net (code "73") (name "unconnected-(DS400-N.C.-Pad33)") (class "Default")
      (node (ref "DS400") (pin "33") (pinfunction "N.C._33") (pintype "passive"))
    )
    (net (code "74") (name "unconnected-(DS400-N.C.-Pad38)") (class "Default")
      (node (ref "DS400") (pin "38") (pinfunction "N.C._38") (pintype "passive"))
    )
    (net (code "75") (name "unconnected-(DS400-N.C.-Pad39)") (class "Default")
      (node (ref "DS400") (pin "39") (pinfunction "N.C._39") (pintype "passive"))
    )
    (net (code "76") (name "unconnected-(IC400-PadEP)") (class "Default")
      (node (ref "IC400") (pin "EP") (pinfunction "EP_EP") (pintype "passive"))
    )
    (net (code "77") (name "unconnected-(IC401-COM1-Pad7)") (class "Default")
      (node (ref "IC401") (pin "7") (pinfunction "COM1_7") (pintype "passive"))
    )
    (net (code "78") (name "unconnected-(IC401-COM2-Pad8)") (class "Default")
      (node (ref "IC401") (pin "8") (pinfunction "COM2_8") (pintype "passive"))
    )
    (net (code "79") (name "unconnected-(IC401-COM3-Pad9)") (class "Default")
      (node (ref "IC401") (pin "9") (pinfunction "COM3_9") (pintype "passive"))
    )
    (net (code "80") (name "unconnected-(IC401-SEG32-Pad2)") (class "Default")
      (node (ref "IC401") (pin "2") (pinfunction "SEG32_2") (pintype "passive"))
    )
    (net (code "81") (name "unconnected-(IC401-SEG33-Pad3)") (class "Default")
      (node (ref "IC401") (pin "3") (pinfunction "SEG33_3") (pintype "passive"))
    )
    (net (code "82") (name "unconnected-(IC401-SEG34-Pad4)") (class "Default")
      (node (ref "IC401") (pin "4") (pinfunction "SEG34_4") (pintype "passive"))
    )
    (net (code "83") (name "unconnected-(IC401-SEG35-Pad5)") (class "Default")
      (node (ref "IC401") (pin "5") (pinfunction "SEG35_5") (pintype "passive"))
    )
    (net (code "84") (name "unconnected-(IC402-PadEP)") (class "Default")
      (node (ref "IC402") (pin "EP") (pinfunction "EP_EP") (pintype "passive"))
    )
    (net (code "85") (name "unconnected-(IC403-NC-Pad3)") (class "Default")
      (node (ref "IC403") (pin "3") (pinfunction "NC_3") (pintype "passive+no_connect"))
    )
    (net (code "86") (name "unconnected-(IC403-NC-Pad7)") (class "Default")
      (node (ref "IC403") (pin "7") (pinfunction "NC_7") (pintype "passive+no_connect"))
    )
    (net (code "87") (name "unconnected-(IC404-NC-Pad3)") (class "Default")
      (node (ref "IC404") (pin "3") (pinfunction "NC_3") (pintype "passive+no_connect"))
    )
    (net (code "88") (name "unconnected-(IC404-NC-Pad7)") (class "Default")
      (node (ref "IC404") (pin "7") (pinfunction "NC_7") (pintype "passive+no_connect"))
    )
    (net (code "89") (name "unconnected-(IC405-NC-Pad3)") (class "Default")
      (node (ref "IC405") (pin "3") (pinfunction "NC_3") (pintype "passive+no_connect"))
    )
    (net (code "90") (name "unconnected-(IC405-NC-Pad7)") (class "Default")
      (node (ref "IC405") (pin "7") (pinfunction "NC_7") (pintype "passive+no_connect"))
    )
    (net (code "91") (name "unconnected-(J400-Pad20)") (class "Default")
      (node (ref "J400") (pin "20") (pinfunction "20_20") (pintype "passive"))
    )
    (net (code "92") (name "unconnected-(SW400-Pad2)") (class "Default")
      (node (ref "SW400") (pin "2") (pinfunction "2_2") (pintype "passive"))
    )
    (net (code "93") (name "unconnected-(SW400-Pad3)") (class "Default")
      (node (ref "SW400") (pin "3") (pinfunction "3_3") (pintype "passive"))
    )
    (net (code "94") (name "unconnected-(SW401-Pad2)") (class "Default")
      (node (ref "SW401") (pin "2") (pinfunction "2_2") (pintype "passive"))
    )
    (net (code "95") (name "unconnected-(SW401-Pad3)") (class "Default")
      (node (ref "SW401") (pin "3") (pinfunction "3_3") (pintype "passive"))
    )
    (net (code "96") (name "unconnected-(SW402-Pad2)") (class "Default")
      (node (ref "SW402") (pin "2") (pinfunction "2_2") (pintype "passive"))
    )
    (net (code "97") (name "unconnected-(SW402-Pad3)") (class "Default")
      (node (ref "SW402") (pin "3") (pinfunction "3_3") (pintype "passive"))
    )
    (net (code "98") (name "unconnected-(SW403-Pad2)") (class "Default")
      (node (ref "SW403") (pin "2") (pinfunction "2_2") (pintype "passive"))
    )
    (net (code "99") (name "unconnected-(SW403-Pad3)") (class "Default")
      (node (ref "SW403") (pin "3") (pinfunction "3_3") (pintype "passive"))
    )
    (net (code "100") (name "unconnected-(SW404-Pad2)") (class "Default")
      (node (ref "SW404") (pin "2") (pinfunction "2_2") (pintype "passive"))
    )
    (net (code "101") (name "unconnected-(SW404-Pad3)") (class "Default")
      (node (ref "SW404") (pin "3") (pinfunction "3_3") (pintype "passive"))
    )
  )
)
